# Power.net
KiCad netlist of a schematic drawn in Altium Designer
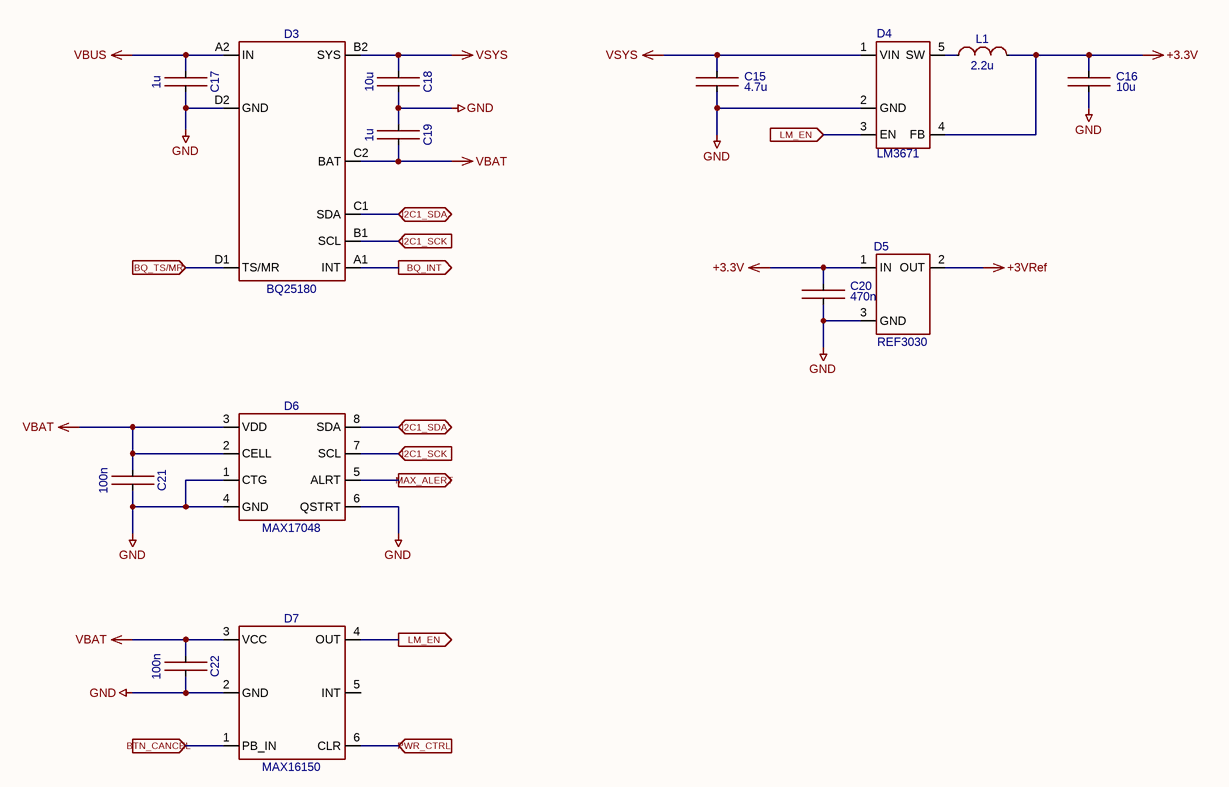
[diagram p0: Power.SchDoc]

(export (version "E")
  (design (tool "Eeschema 10.0.6"))
  (components
    (comp (ref "C15")
      (value "4.7u")
      (footprint "CAPC1608X09N")
      (description "GRM188R61A475K")
      (libsource (lib "Capasitors") (part "C0603-4.7u-10V-X5R-10%"))
    )
    (comp (ref "C16")
      (value "10u")
      (footprint "CAPC1608X09N")
      (description "GRM188R60J106ME47D")
      (libsource (lib "Capasitors") (part "C0603-10u-6.3V-X5R-20%"))
    )
    (comp (ref "C17")
      (value "1u")
      (footprint "CAPC1608X09N")
      (description "GRM188R71E105KA12D")
      (libsource (lib "Capasitors") (part "C0603-1u-25V-X7R-10%"))
    )
    (comp (ref "C18")
      (value "10u")
      (footprint "CAPC1608X09N")
      (description "GRM188R60J106ME47D")
      (libsource (lib "Capasitors") (part "C0603-10u-6.3V-X5R-20%"))
    )
    (comp (ref "C19")
      (value "1u")
      (footprint "CAPC1608X09N")
      (description "GRM188R71E105KA12D")
      (libsource (lib "Capasitors") (part "C0603-1u-25V-X7R-10%"))
    )
    (comp (ref "C20")
      (value "470n")
      (footprint "CAPC1608X09N")
      (description "GRM188R71C474KA88D")
      (libsource (lib "Capasitors") (part "C0603-470n-16V-X7R-10%"))
    )
    (comp (ref "C21")
      (value "100n")
      (footprint "CAPC1608X09N")
      (description "GRM188R71E104KA01D")
      (libsource (lib "Capasitors") (part "C0603-100n-25V-X7R-10%"))
    )
    (comp (ref "C22")
      (value "100n")
      (footprint "CAPC1608X09N")
      (description "GRM188R71E104KA01D")
      (libsource (lib "Capasitors") (part "C0603-100n-25V-X7R-10%"))
    )
    (comp (ref "D3")
      (value "BQ25180")
      (footprint "TI DSBGA (YBG0008)")
      (description "1-A Li-ion I²C programmable charger with regulated power path in WCSP package")
      (libsource (lib "Integrated Circuits") (part "BQ25180YBGR"))
    )
    (comp (ref "D4")
      (value "LM3671")
      (footprint "TI DBV (R-PDSO-G5)")
      (libsource (lib "Integrated Circuits") (part "LM3671MF-3.3/NOPB"))
    )
    (comp (ref "D5")
      (value "REF3030")
      (footprint "TI DBZ (R-PDSO-G3)")
      (libsource (lib "Integrated Circuits") (part "REF3030AIDBZT"))
    )
    (comp (ref "D6")
      (value "MAX17048")
      (footprint "MAXIM 8 TDFN-EP (T822-3)")
      (libsource (lib "Integrated Circuits") (part "MAX17048G"))
    )
    (comp (ref "D7")
      (value "MAX16150")
      (footprint "MAXIM WLP6 (21-0058)")
      (libsource (lib "Integrated Circuits") (part "MAX16150A"))
    )
    (comp (ref "L1")
      (value "2.2u")
      (footprint "Murata LQH43CN")
      (description "LQH43CN2R2M03L")
      (libsource (lib "Inductors") (part "L1812-2.2u-0.9A-20%"))
    )
  )
  (nets
    (net (code "1") (name "+3.3V") (class "Default")
      (node (ref "C16") (pin "2") (pinfunction "2_2") (pintype "passive"))
      (node (ref "C20") (pin "2") (pinfunction "2_2") (pintype "passive"))
      (node (ref "D4") (pin "4") (pinfunction "FB_4") (pintype "passive"))
      (node (ref "D5") (pin "1") (pinfunction "IN_1") (pintype "passive"))
      (node (ref "L1") (pin "2") (pinfunction "2_2") (pintype "passive"))
    )
    (net (code "2") (name "+3VRef") (class "Default")
      (node (ref "D5") (pin "2") (pinfunction "OUT_2") (pintype "passive"))
    )
    (net (code "3") (name "/BQ_INT") (class "Default")
      (node (ref "D3") (pin "A1") (pinfunction "INT_A1") (pintype "passive"))
    )
    (net (code "4") (name "/BQ_TS{slash}MR") (class "Default")
      (node (ref "D3") (pin "D1") (pinfunction "TS/MR_D1") (pintype "passive"))
    )
    (net (code "5") (name "/BTN_CANCEL") (class "Default")
      (node (ref "D7") (pin "1") (pinfunction "PB_IN_1") (pintype "passive"))
    )
    (net (code "6") (name "/I2C1_SCK") (class "Default")
      (node (ref "D3") (pin "B1") (pinfunction "SCL_B1") (pintype "passive"))
      (node (ref "D6") (pin "7") (pinfunction "SCL_7") (pintype "passive"))
    )
    (net (code "7") (name "/I2C1_SDA") (class "Default")
      (node (ref "D3") (pin "C1") (pinfunction "SDA_C1") (pintype "passive"))
      (node (ref "D6") (pin "8") (pinfunction "SDA_8") (pintype "passive"))
    )
    (net (code "8") (name "/LM_EN") (class "Default")
      (node (ref "D4") (pin "3") (pinfunction "EN_3") (pintype "passive"))
      (node (ref "D7") (pin "4") (pinfunction "OUT_4") (pintype "passive"))
    )
    (net (code "9") (name "/MAX_ALERT") (class "Default")
      (node (ref "D6") (pin "5") (pinfunction "ALRT_5") (pintype "passive"))
    )
    (net (code "10") (name "/PWR_CTRL") (class "Default")
      (node (ref "D7") (pin "6") (pinfunction "CLR_6") (pintype "passive"))
    )
    (net (code "11") (name "GND") (class "Default")
      (node (ref "C15") (pin "1") (pinfunction "1_1") (pintype "passive"))
      (node (ref "C16") (pin "1") (pinfunction "1_1") (pintype "passive"))
      (node (ref "C17") (pin "2") (pinfunction "2_2") (pintype "passive"))
      (node (ref "C18") (pin "2") (pinfunction "2_2") (pintype "passive"))
      (node (ref "C19") (pin "1") (pinfunction "1_1") (pintype "passive"))
      (node (ref "C20") (pin "1") (pinfunction "1_1") (pintype "passive"))
      (node (ref "C21") (pin "2") (pinfunction "2_2") (pintype "passive"))
      (node (ref "C22") (pin "2") (pinfunction "2_2") (pintype "passive"))
      (node (ref "D3") (pin "D2") (pinfunction "GND_D2") (pintype "passive"))
      (node (ref "D4") (pin "2") (pinfunction "GND_2") (pintype "passive"))
      (node (ref "D5") (pin "3") (pinfunction "GND_3") (pintype "passive"))
      (node (ref "D6") (pin "1") (pinfunction "CTG_1") (pintype "passive"))
      (node (ref "D6") (pin "4") (pinfunction "GND_4") (pintype "passive"))
      (node (ref "D6") (pin "6") (pinfunction "QSTRT_6") (pintype "passive"))
      (node (ref "D7") (pin "2") (pinfunction "GND_2") (pintype "passive"))
    )
    (net (code "12") (name "Net-(D4-SW)") (class "Default")
      (node (ref "D4") (pin "5") (pinfunction "SW_5") (pintype "passive"))
      (node (ref "L1") (pin "1") (pinfunction "1_1") (pintype "passive"))
    )
    (net (code "13") (name "VBAT") (class "Default")
      (node (ref "C19") (pin "2") (pinfunction "2_2") (pintype "passive"))
      (node (ref "C21") (pin "1") (pinfunction "1_1") (pintype "passive"))
      (node (ref "C22") (pin "1") (pinfunction "1_1") (pintype "passive"))
      (node (ref "D3") (pin "C2") (pinfunction "BAT_C2") (pintype "passive"))
      (node (ref "D6") (pin "2") (pinfunction "CELL_2") (pintype "passive"))
      (node (ref "D6") (pin "3") (pinfunction "VDD_3") (pintype "passive"))
      (node (ref "D7") (pin "3") (pinfunction "VCC_3") (pintype "passive"))
    )
    (net (code "14") (name "VBUS") (class "Default")
      (node (ref "C17") (pin "1") (pinfunction "1_1") (pintype "passive"))
      (node (ref "D3") (pin "A2") (pinfunction "IN_A2") (pintype "passive"))
    )
    (net (code "15") (name "VSYS") (class "Default")
      (node (ref "C15") (pin "2") (pinfunction "2_2") (pintype "passive"))
      (node (ref "C18") (pin "1") (pinfunction "1_1") (pintype "passive"))
      (node (ref "D3") (pin "B2") (pinfunction "SYS_B2") (pintype "passive"))
      (node (ref "D4") (pin "1") (pinfunction "VIN_1") (pintype "passive"))
    )
    (net (code "16") (name "unconnected-(D7-INT-Pad5)") (class "Default")
      (node (ref "D7") (pin "5") (pinfunction "INT_5") (pintype "passive"))
    )
  )
)
